# breakout.net
KiCad netlist of a schematic drawn in Altium Designer
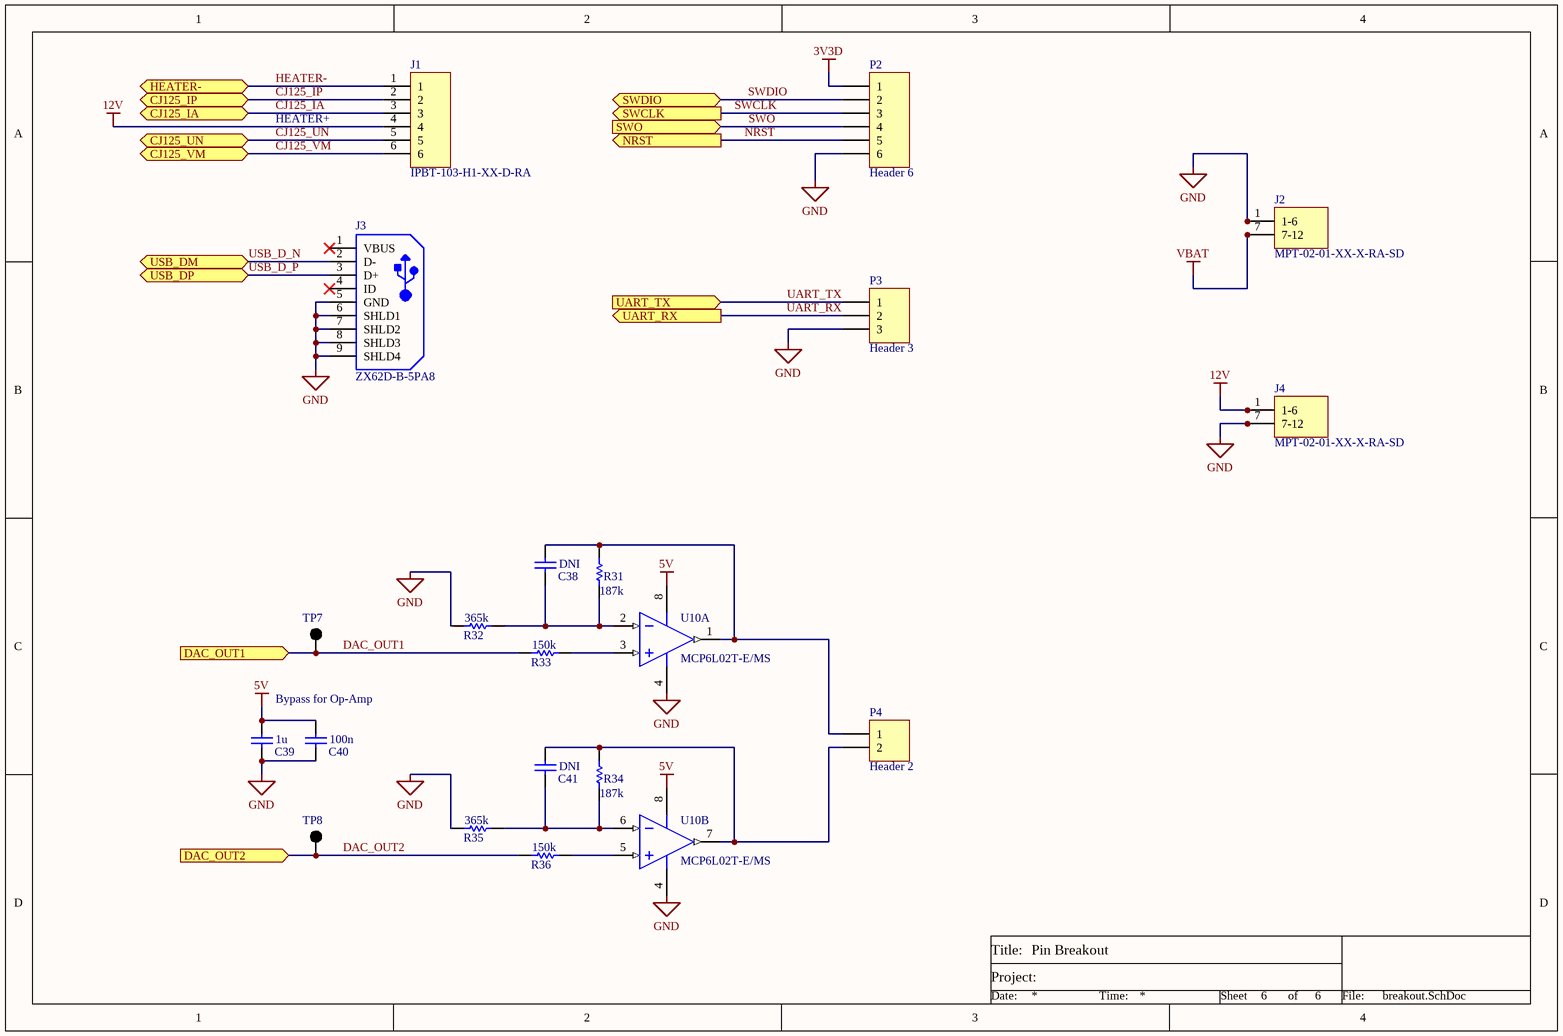
[diagram p0: breakout.SchDoc]

(export (version "E")
  (design (tool "Eeschema 10.0.6"))
  (components
    (comp (ref "C38")
      (value "DNI")
      (footprint "0805")
      (description "Generic 0805 Capacitor")
      (libsource (lib "symbol_library") (part "C_0805"))
    )
    (comp (ref "C39")
      (value "1u")
      (footprint "0805")
      (description "Generic 0805 Capacitor")
      (libsource (lib "symbol_library") (part "C_0805"))
    )
    (comp (ref "C40")
      (value "100n")
      (footprint "0805")
      (description "Generic 0805 Capacitor")
      (libsource (lib "symbol_library") (part "C_0805"))
    )
    (comp (ref "C41")
      (value "DNI")
      (footprint "0805")
      (description "Generic 0805 Capacitor")
      (libsource (lib "symbol_library") (part "C_0805"))
    )
    (comp (ref "J1")
      (value "IPBT-103-H1-XX-D-RA")
      (footprint "IPBT-103-H1-XX-D-RA")
      (description "0.165 INCH DOUBLE ROW TERMINAL ASSEMBLY")
      (libsource (lib "symbol_library") (part "IPBT-103-H1-XX-D-RA"))
    )
    (comp (ref "J2")
      (value "MPT-02-01-XX-X-RA-SD")
      (footprint "MPT-02-01-XX-X-RA-SD")
      (libsource (lib "symbol_library") (part "MPT-02-01-XX-X-RA-SD"))
    )
    (comp (ref "J3")
      (value "ZX62D-B-5PA8")
      (footprint "HIRO-ZX62D-B-5PA8_V")
      (description "Micro-USB Connector Meeting USB 2.0 Standard, -30 to 85 degC, 5-Pin SMD, RoHS, Tape and Reel")
      (fields (field (name "MANUFACTURER") "HiroseElectric"))
      (libsource (lib "symbol_library") (part "Micro_USB"))
    )
    (comp (ref "J4")
      (value "MPT-02-01-XX-X-RA-SD")
      (footprint "MPT-02-01-XX-X-RA-SD")
      (libsource (lib "symbol_library") (part "MPT-02-01-XX-X-RA-SD"))
    )
    (comp (ref "P2")
      (value "Header 6")
      (footprint "HDR1X6")
      (description "Header, 6-Pin")
      (fields (field (name "PUBLISHER") "Altium Limited"))
      (libsource (lib "Miscellaneous Connectors") (part "Header 6"))
    )
    (comp (ref "P3")
      (value "Header 3")
      (footprint "HDR1X3")
      (description "Header, 3-Pin")
      (fields (field (name "PUBLISHER") "Altium Limited"))
      (libsource (lib "Miscellaneous Connectors") (part "Header 3"))
    )
    (comp (ref "P4")
      (value "Header 2")
      (footprint "HDR1X2")
      (description "Header, 2-Pin")
      (fields (field (name "PUBLISHER") "Altium Limited"))
      (libsource (lib "Miscellaneous Connectors") (part "Header 2"))
    )
    (comp (ref "R31")
      (value "187k")
      (footprint "0603")
      (description "Generic 0603 Resistor")
      (libsource (lib "symbol_library") (part "R_0603"))
    )
    (comp (ref "R32")
      (value "365k")
      (footprint "0603")
      (description "Generic 0603 Resistor")
      (libsource (lib "symbol_library") (part "R_0603"))
    )
    (comp (ref "R33")
      (value "150k")
      (footprint "0603")
      (description "Generic 0603 Resistor")
      (libsource (lib "symbol_library") (part "R_0603"))
    )
    (comp (ref "R34")
      (value "187k")
      (footprint "0603")
      (description "Generic 0603 Resistor")
      (libsource (lib "symbol_library") (part "R_0603"))
    )
    (comp (ref "R35")
      (value "365k")
      (footprint "0603")
      (description "Generic 0603 Resistor")
      (libsource (lib "symbol_library") (part "R_0603"))
    )
    (comp (ref "R36")
      (value "150k")
      (footprint "0603")
      (description "Generic 0603 Resistor")
      (libsource (lib "symbol_library") (part "R_0603"))
    )
    (comp (ref "TP7")
      (value "5001")
      (footprint "KSTN-5001")
      (description "Test Point, Black, 1-Pin THD, RoHS, Bulk")
      (fields (field (name "MANUFACTURER") "Keystone"))
      (libsource (lib "symbol_library") (part "TP5001"))
    )
    (comp (ref "TP8")
      (value "5001")
      (footprint "KSTN-5001")
      (description "Test Point, Black, 1-Pin THD, RoHS, Bulk")
      (fields (field (name "MANUFACTURER") "Keystone"))
      (libsource (lib "symbol_library") (part "TP5001"))
    )
    (comp (ref "U10")
      (value "MCP6L02T-E/MS")
      (footprint "MSOP8_M")
      (description "1 MHz, 85 渭A Dual Op Amp, 8-Pin MSOP, Extended Temperature Range, Tape and Reel")
      (libsource (lib "symbol_library") (part "MCP6L02"))
    )
  )
  (nets
    (net (code "1") (name "/CJ125_IA") (class "Default")
      (node (ref "J1") (pin "3") (pinfunction "3_3") (pintype "passive"))
    )
    (net (code "2") (name "/CJ125_IP") (class "Default")
      (node (ref "J1") (pin "2") (pinfunction "2_2") (pintype "passive"))
    )
    (net (code "3") (name "/CJ125_UN") (class "Default")
      (node (ref "J1") (pin "5") (pinfunction "5_5") (pintype "passive"))
    )
    (net (code "4") (name "/CJ125_VM") (class "Default")
      (node (ref "J1") (pin "6") (pinfunction "6_6") (pintype "passive"))
    )
    (net (code "5") (name "/DAC_OUT1") (class "Default")
      (node (ref "R33") (pin "1") (pinfunction "1_1") (pintype "passive"))
      (node (ref "TP7") (pin "1") (pintype "passive"))
    )
    (net (code "6") (name "/DAC_OUT2") (class "Default")
      (node (ref "R36") (pin "1") (pinfunction "1_1") (pintype "passive"))
      (node (ref "TP8") (pin "1") (pintype "passive"))
    )
    (net (code "7") (name "/HEATER-") (class "Default")
      (node (ref "J1") (pin "1") (pinfunction "1_1") (pintype "passive"))
    )
    (net (code "8") (name "/NRST") (class "Default")
      (node (ref "P2") (pin "5") (pinfunction "5_5") (pintype "passive"))
    )
    (net (code "9") (name "/SWCLK") (class "Default")
      (node (ref "P2") (pin "3") (pinfunction "3_3") (pintype "passive"))
    )
    (net (code "10") (name "/SWDIO") (class "Default")
      (node (ref "P2") (pin "2") (pinfunction "2_2") (pintype "passive"))
    )
    (net (code "11") (name "/SWO") (class "Default")
      (node (ref "P2") (pin "4") (pinfunction "4_4") (pintype "passive"))
    )
    (net (code "12") (name "/UART_RX") (class "Default")
      (node (ref "P3") (pin "2") (pinfunction "2_2") (pintype "passive"))
    )
    (net (code "13") (name "/UART_TX") (class "Default")
      (node (ref "P3") (pin "1") (pinfunction "1_1") (pintype "passive"))
    )
    (net (code "14") (name "/USB_D_N") (class "Default")
      (node (ref "J3") (pin "2") (pinfunction "D-_2") (pintype "passive"))
    )
    (net (code "15") (name "/USB_D_P") (class "Default")
      (node (ref "J3") (pin "3") (pinfunction "D+_3") (pintype "passive"))
    )
    (net (code "16") (name "3V3D") (class "Default")
      (node (ref "P2") (pin "1") (pinfunction "1_1") (pintype "passive"))
    )
    (net (code "17") (name "5V") (class "Default")
      (node (ref "C39") (pin "2") (pinfunction "2_2") (pintype "passive"))
      (node (ref "C40") (pin "2") (pinfunction "2_2") (pintype "passive"))
      (node (ref "U10") (pin "8") (pinfunction "VDD_8") (pintype "power_in"))
    )
    (net (code "18") (name "12V") (class "Default")
      (node (ref "J1") (pin "4") (pinfunction "4_4") (pintype "passive"))
      (node (ref "J4") (pin "1") (pinfunction "1-6_1") (pintype "passive"))
      (node (ref "J4") (pin "2") (pinfunction "2_2") (pintype "passive"))
      (node (ref "J4") (pin "3") (pinfunction "3_3") (pintype "passive"))
      (node (ref "J4") (pin "4") (pinfunction "4_4") (pintype "passive"))
      (node (ref "J4") (pin "5") (pinfunction "5_5") (pintype "passive"))
      (node (ref "J4") (pin "6") (pinfunction "6_6") (pintype "passive"))
    )
    (net (code "19") (name "GND") (class "Default")
      (node (ref "C39") (pin "1") (pinfunction "1_1") (pintype "passive"))
      (node (ref "C40") (pin "1") (pinfunction "1_1") (pintype "passive"))
      (node (ref "J2") (pin "1") (pinfunction "1-6_1") (pintype "passive"))
      (node (ref "J2") (pin "2") (pinfunction "2_2") (pintype "passive"))
      (node (ref "J2") (pin "3") (pinfunction "3_3") (pintype "passive"))
      (node (ref "J2") (pin "4") (pinfunction "4_4") (pintype "passive"))
      (node (ref "J2") (pin "5") (pinfunction "5_5") (pintype "passive"))
      (node (ref "J2") (pin "6") (pinfunction "6_6") (pintype "passive"))
      (node (ref "J3") (pin "5") (pinfunction "GND_5") (pintype "passive"))
      (node (ref "J3") (pin "6") (pinfunction "SHLD1_6") (pintype "passive"))
      (node (ref "J3") (pin "7") (pinfunction "SHLD2_7") (pintype "passive"))
      (node (ref "J3") (pin "8") (pinfunction "SHLD3_8") (pintype "passive"))
      (node (ref "J3") (pin "9") (pinfunction "SHLD4_9") (pintype "passive"))
      (node (ref "J4") (pin "10") (pinfunction "10_10") (pintype "passive"))
      (node (ref "J4") (pin "11") (pinfunction "11_11") (pintype "passive"))
      (node (ref "J4") (pin "12") (pinfunction "12_12") (pintype "passive"))
      (node (ref "J4") (pin "7") (pinfunction "7-12_7") (pintype "passive"))
      (node (ref "J4") (pin "8") (pinfunction "8_8") (pintype "passive"))
      (node (ref "J4") (pin "9") (pinfunction "9_9") (pintype "passive"))
      (node (ref "P2") (pin "6") (pinfunction "6_6") (pintype "passive"))
      (node (ref "P3") (pin "3") (pinfunction "3_3") (pintype "passive"))
      (node (ref "R32") (pin "1") (pinfunction "1_1") (pintype "passive"))
      (node (ref "R35") (pin "1") (pinfunction "1_1") (pintype "passive"))
      (node (ref "U10") (pin "4") (pinfunction "VSS_4") (pintype "power_in"))
    )
    (net (code "20") (name "Net-(U10A-VINA+)") (class "Default")
      (node (ref "R33") (pin "2") (pinfunction "2_2") (pintype "passive"))
      (node (ref "U10") (pin "3") (pinfunction "VINA+_3") (pintype "input"))
    )
    (net (code "21") (name "Net-(U10A-VINA-)") (class "Default")
      (node (ref "C38") (pin "1") (pinfunction "1_1") (pintype "passive"))
      (node (ref "R31") (pin "1") (pinfunction "1_1") (pintype "passive"))
      (node (ref "R32") (pin "2") (pinfunction "2_2") (pintype "passive"))
      (node (ref "U10") (pin "2") (pinfunction "VINA-_2") (pintype "input"))
    )
    (net (code "22") (name "Net-(U10A-VOUTA)") (class "Default")
      (node (ref "C38") (pin "2") (pinfunction "2_2") (pintype "passive"))
      (node (ref "P4") (pin "1") (pinfunction "1_1") (pintype "passive"))
      (node (ref "R31") (pin "2") (pinfunction "2_2") (pintype "passive"))
      (node (ref "U10") (pin "1") (pinfunction "VOUTA_1") (pintype "output"))
    )
    (net (code "23") (name "Net-(U10B-VINB+)") (class "Default")
      (node (ref "R36") (pin "2") (pinfunction "2_2") (pintype "passive"))
      (node (ref "U10") (pin "5") (pinfunction "VINB+_5") (pintype "input"))
    )
    (net (code "24") (name "Net-(U10B-VINB-)") (class "Default")
      (node (ref "C41") (pin "1") (pinfunction "1_1") (pintype "passive"))
      (node (ref "R34") (pin "1") (pinfunction "1_1") (pintype "passive"))
      (node (ref "R35") (pin "2") (pinfunction "2_2") (pintype "passive"))
      (node (ref "U10") (pin "6") (pinfunction "VINB-_6") (pintype "input"))
    )
    (net (code "25") (name "Net-(U10B-VOUTB)") (class "Default")
      (node (ref "C41") (pin "2") (pinfunction "2_2") (pintype "passive"))
      (node (ref "P4") (pin "2") (pinfunction "2_2") (pintype "passive"))
      (node (ref "R34") (pin "2") (pinfunction "2_2") (pintype "passive"))
      (node (ref "U10") (pin "7") (pinfunction "VOUTB_7") (pintype "output"))
    )
    (net (code "26") (name "VBAT") (class "Default")
      (node (ref "J2") (pin "10") (pinfunction "10_10") (pintype "passive"))
      (node (ref "J2") (pin "11") (pinfunction "11_11") (pintype "passive"))
      (node (ref "J2") (pin "12") (pinfunction "12_12") (pintype "passive"))
      (node (ref "J2") (pin "7") (pinfunction "7-12_7") (pintype "passive"))
      (node (ref "J2") (pin "8") (pinfunction "8_8") (pintype "passive"))
      (node (ref "J2") (pin "9") (pinfunction "9_9") (pintype "passive"))
    )
    (net (code "27") (name "unconnected-(J3-ID-Pad4)") (class "Default")
      (node (ref "J3") (pin "4") (pinfunction "ID_4") (pintype "passive+no_connect"))
    )
    (net (code "28") (name "unconnected-(J3-VBUS-Pad1)") (class "Default")
      (node (ref "J3") (pin "1") (pinfunction "VBUS_1") (pintype "passive+no_connect"))
    )
  )
)
